# 918B.net
KiCad netlist of a schematic drawn in EAGLE
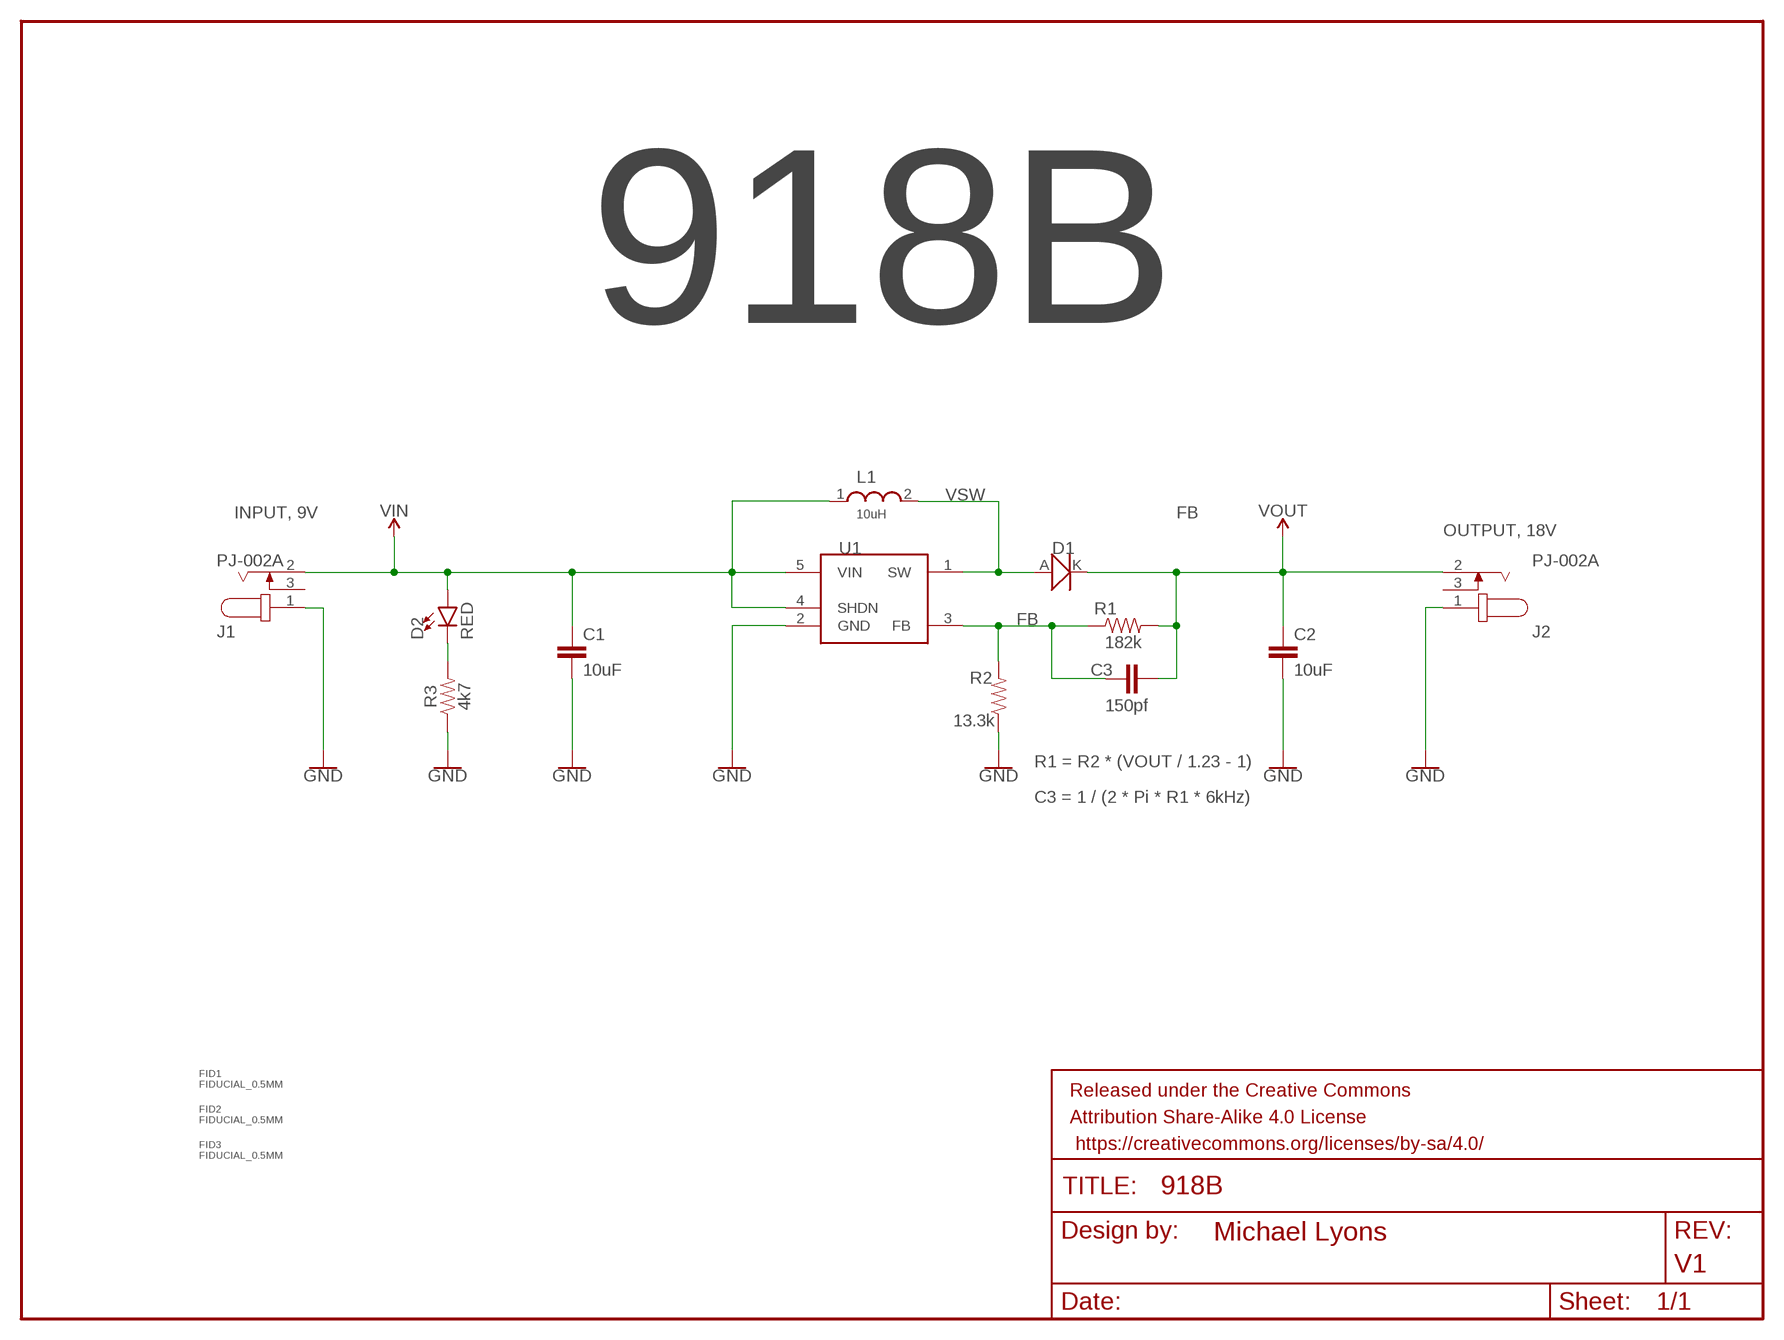
[diagram p0: schematic, sheet 1]

(export (version "E")
  (design (tool "Eeschema 10.0.6"))
  (components
    (comp (ref "C1")
      (value "10uF")
      (footprint "eagle-import:0805")
      (fields (field (name "MPN") "GRM21BR61E106KA73L"))
      (libsource (lib "eagle-import") (part "10UF-0805-25V-10%"))
    )
    (comp (ref "C2")
      (value "10uF")
      (footprint "eagle-import:0805")
      (fields (field (name "MPN") "GRM21BR61E106KA73L"))
      (libsource (lib "eagle-import") (part "10UF-0805-25V-10%"))
    )
    (comp (ref "C3")
      (value "150pf")
      (footprint "eagle-import:0402")
      (fields (field (name "MPN") "C0402C151J5GACTU"))
      (libsource (lib "eagle-import") (part "CAP-0402"))
    )
    (comp (ref "D1")
      (value "PMEG4030EP,115")
      (footprint "eagle-import:PMEG4030EP,115")
      (libsource (lib "eagle-import") (part "PMEG4030EP,115"))
    )
    (comp (ref "D2")
      (value "RED")
      (footprint "eagle-import:LED-0603")
      (fields (field (name "MPN") "HSMC-C190"))
      (libsource (lib "eagle-import") (part "LED-RED0603"))
    )
    (comp (ref "FID1")
      (value "FIDUCIAL_0.5MM")
      (footprint "eagle-import:FIDUCIAL_0.5MM")
      (fields (field (name "HOUSEPART") "NO"))
      (libsource (lib "eagle-import") (part "FIDUCIAL_0.5MM"))
    )
    (comp (ref "FID2")
      (value "FIDUCIAL_0.5MM")
      (footprint "eagle-import:FIDUCIAL_0.5MM")
      (fields (field (name "HOUSEPART") "NO"))
      (libsource (lib "eagle-import") (part "FIDUCIAL_0.5MM"))
    )
    (comp (ref "FID3")
      (value "FIDUCIAL_0.5MM")
      (footprint "eagle-import:FIDUCIAL_0.5MM")
      (fields (field (name "HOUSEPART") "NO"))
      (libsource (lib "eagle-import") (part "FIDUCIAL_0.5MM"))
    )
    (comp (ref "FRAME1")
      (value "FRAME-LETTER")
      (footprint "eagle-import:CREATIVE_COMMONS")
      (fields (field (name "DESIGNER") "Michael Lyons") (field (name "REV") "V1"))
      (libsource (lib "eagle-import") (part "FRAME-LETTER"))
    )
    (comp (ref "J1")
      (value "PJ-002A")
      (footprint "eagle-import:CUI_PJ-002A")
      (fields (field (name "MF") "CUI Devices"))
      (libsource (lib "eagle-import") (part "PJ-002A"))
    )
    (comp (ref "J2")
      (value "PJ-002A")
      (footprint "eagle-import:CUI_PJ-002A")
      (fields (field (name "MF") "CUI Devices"))
      (libsource (lib "eagle-import") (part "PJ-002A"))
    )
    (comp (ref "L1")
      (value "10uH")
      (footprint "eagle-import:NR10050T100M")
      (fields (field (name "MPN") "NR10050T100M"))
      (libsource (lib "eagle-import") (part "NR10050T100M"))
    )
    (comp (ref "R1")
      (value "182k")
      (footprint "eagle-import:0402")
      (fields (field (name "MPN") "RC0402FR-07182KL"))
      (libsource (lib "eagle-import") (part "RESISTOR0402"))
    )
    (comp (ref "R2")
      (value "13.3k")
      (footprint "eagle-import:0402")
      (fields (field (name "MPN") "RC0402FR-0713K3L"))
      (libsource (lib "eagle-import") (part "RESISTOR0402"))
    )
    (comp (ref "R3")
      (value "4k7")
      (footprint "eagle-import:0402")
      (fields (field (name "MPN") "RC0402JR-074K7L"))
      (libsource (lib "eagle-import") (part "RESISTOR0402"))
    )
    (comp (ref "U1")
      (value "LMR62014XM")
      (footprint "eagle-import:SOT-23-5")
      (fields (field (name "MPN") "LMR62014XMFX/NOPB"))
      (libsource (lib "eagle-import") (part "LMR62014XM"))
    )
  )
  (nets
    (net (code "1") (name "/FB") (class "Default")
      (node (ref "C3") (pin "1") (pinfunction "1_1") (pintype "passive"))
      (node (ref "R1") (pin "1") (pinfunction "1_1") (pintype "passive"))
      (node (ref "R2") (pin "2") (pinfunction "2_2") (pintype "passive"))
      (node (ref "U1") (pin "3") (pinfunction "FB_3") (pintype "passive"))
    )
    (net (code "2") (name "/VSW") (class "Default")
      (node (ref "D1") (pin "A") (pinfunction "A_A") (pintype "bidirectional"))
      (node (ref "L1") (pin "2") (pinfunction "2_2") (pintype "passive"))
      (node (ref "U1") (pin "1") (pinfunction "SW_1") (pintype "power_in"))
    )
    (net (code "3") (name "GND") (class "Default")
      (node (ref "C1") (pin "2") (pinfunction "2_2") (pintype "passive"))
      (node (ref "C2") (pin "2") (pinfunction "2_2") (pintype "passive"))
      (node (ref "J1") (pin "1") (pinfunction "1_1") (pintype "passive"))
      (node (ref "J2") (pin "1") (pinfunction "1_1") (pintype "passive"))
      (node (ref "R2") (pin "1") (pinfunction "1_1") (pintype "passive"))
      (node (ref "R3") (pin "1") (pinfunction "1_1") (pintype "passive"))
      (node (ref "U1") (pin "2") (pinfunction "GND_2") (pintype "power_in"))
    )
    (net (code "4") (name "Net-(D2-PadC)") (class "Default")
      (node (ref "D2") (pin "C") (pinfunction "C_C") (pintype "passive"))
      (node (ref "R3") (pin "2") (pinfunction "2_2") (pintype "passive"))
    )
    (net (code "5") (name "VIN") (class "Default")
      (node (ref "C1") (pin "1") (pinfunction "1_1") (pintype "passive"))
      (node (ref "D2") (pin "A") (pinfunction "A_A") (pintype "passive"))
      (node (ref "J1") (pin "2") (pinfunction "2_2") (pintype "passive"))
      (node (ref "L1") (pin "1") (pinfunction "1_1") (pintype "passive"))
      (node (ref "U1") (pin "4") (pinfunction "SHDN_4") (pintype "bidirectional"))
      (node (ref "U1") (pin "5") (pinfunction "VIN_5") (pintype "power_in"))
    )
    (net (code "6") (name "VOUT") (class "Default")
      (node (ref "C2") (pin "1") (pinfunction "1_1") (pintype "passive"))
      (node (ref "C3") (pin "2") (pinfunction "2_2") (pintype "passive"))
      (node (ref "D1") (pin "K") (pinfunction "K_K") (pintype "bidirectional"))
      (node (ref "J2") (pin "2") (pinfunction "2_2") (pintype "passive"))
      (node (ref "R1") (pin "2") (pinfunction "2_2") (pintype "passive"))
    )
    (net (code "7") (name "unconnected-(J1-Pad3)") (class "Default")
      (node (ref "J1") (pin "3") (pinfunction "3_3") (pintype "passive"))
    )
    (net (code "8") (name "unconnected-(J2-Pad3)") (class "Default")
      (node (ref "J2") (pin "3") (pinfunction "3_3") (pintype "passive"))
    )
  )
)
